# 2015PCB.net
KiCad netlist of a schematic drawn in Altium Designer
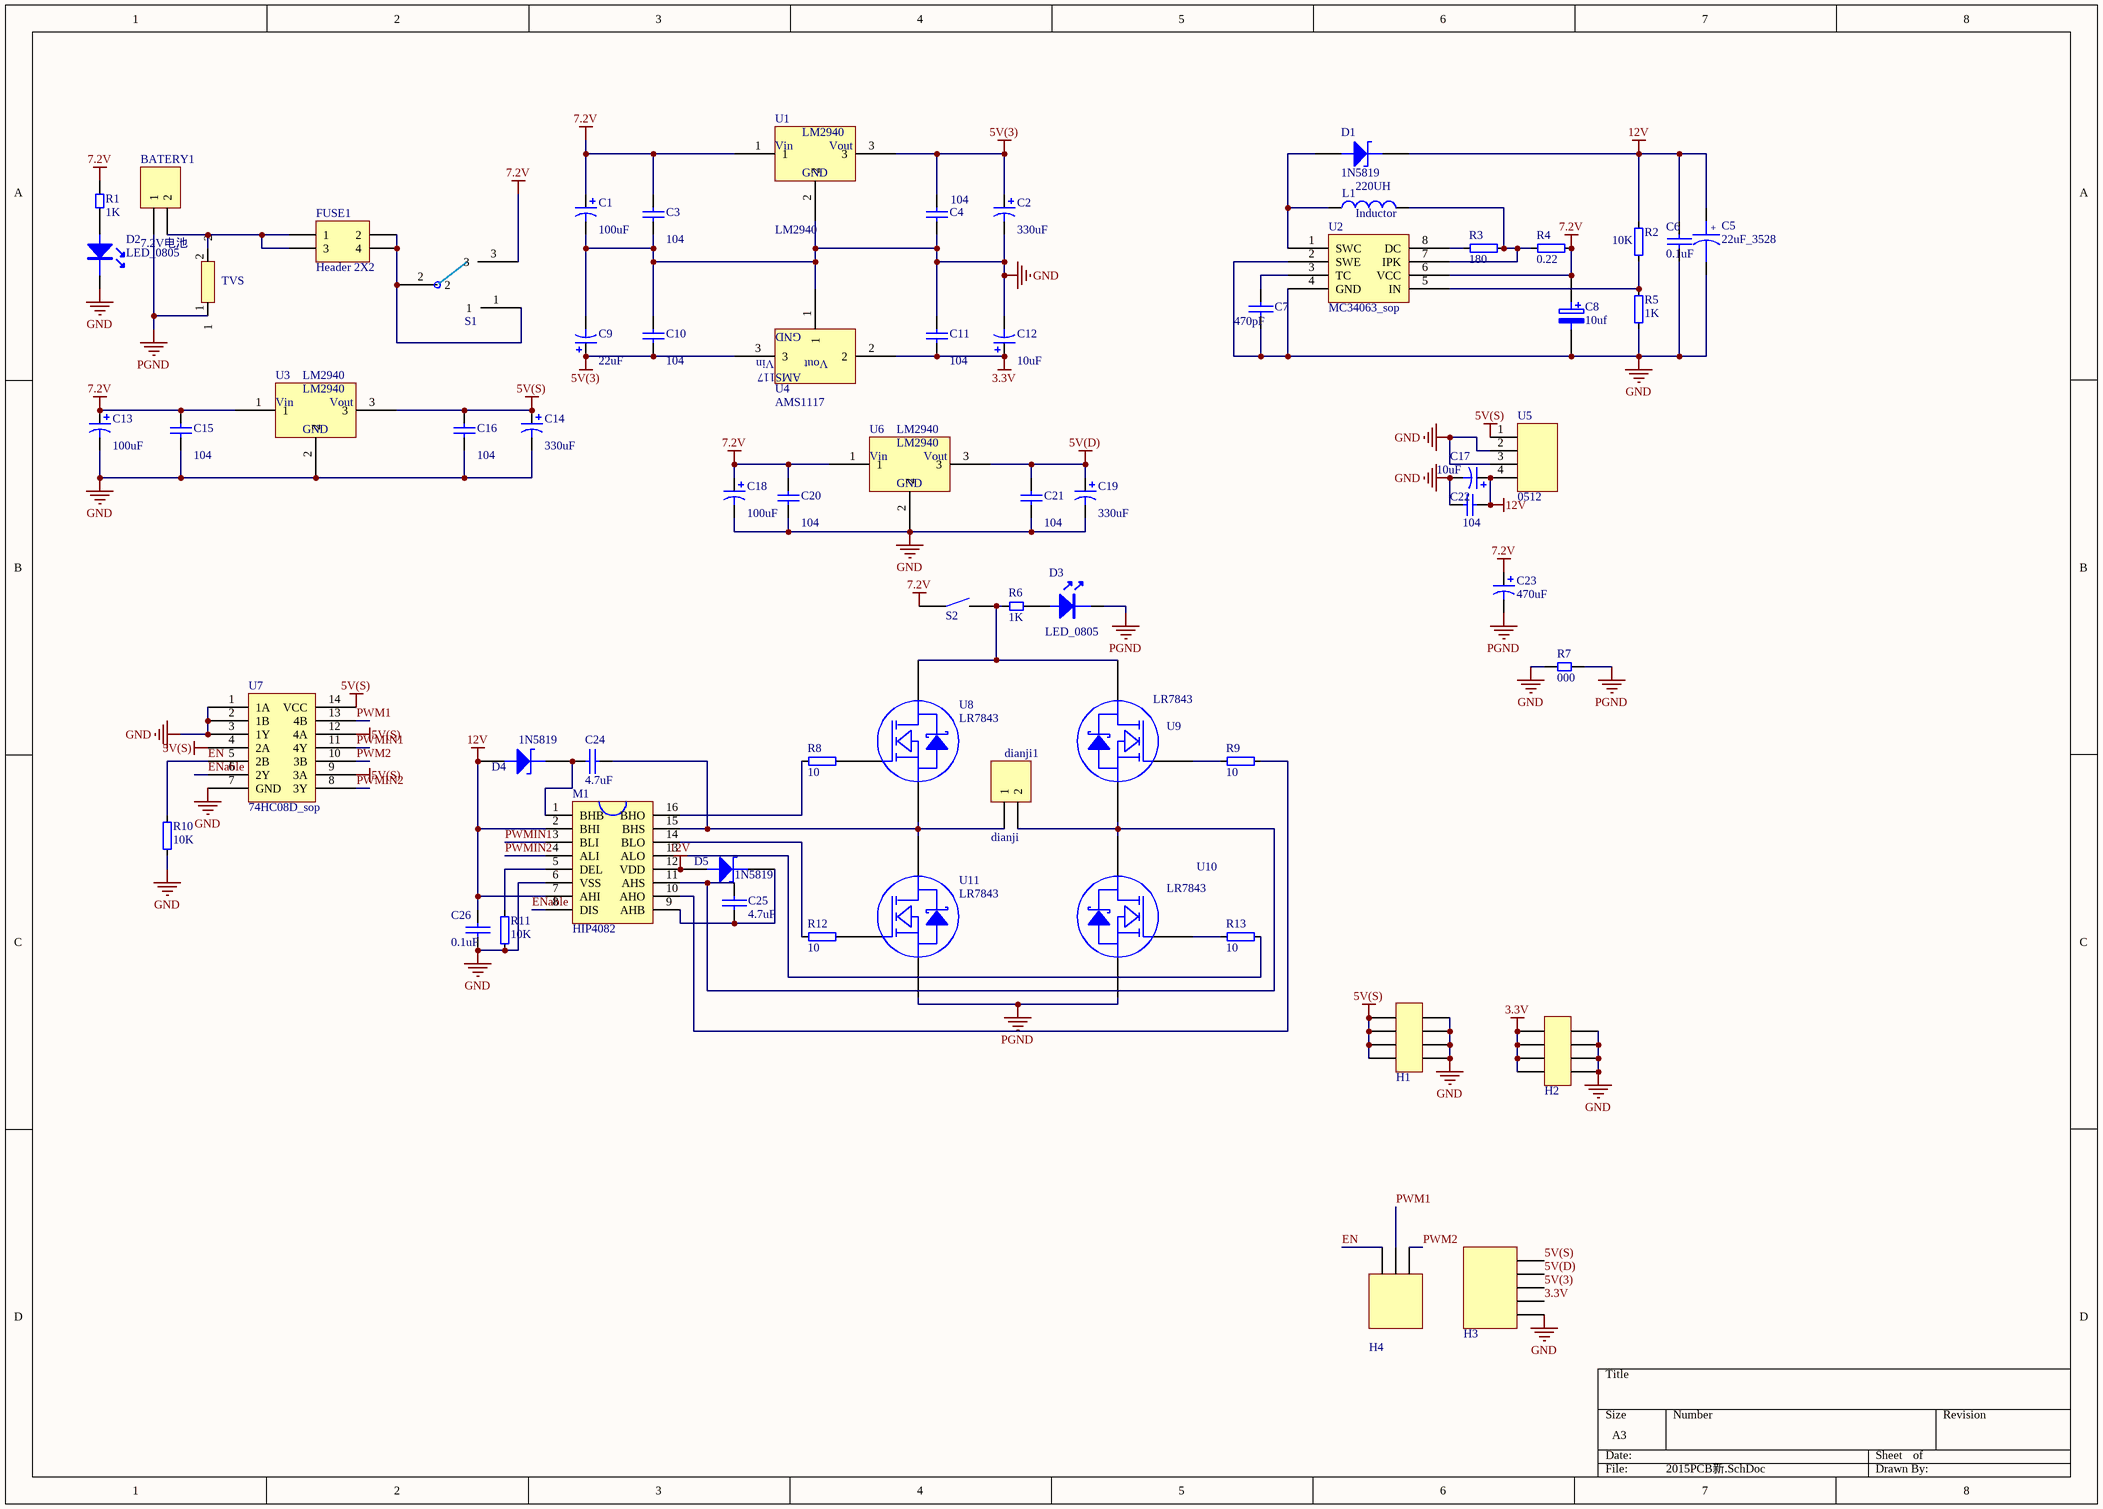
[diagram p0: 2015PCB新.SchDoc]

(export (version "E")
  (design (tool "Eeschema 10.0.6"))
  (components
    (comp (ref "BATERY1")
      (value "7.2V电池")
      (footprint "source:PCBComponent_1")
      (description "Header, 2-Pin")
      (fields (field (name "PUBLISHER") "Altium Limited"))
      (libsource (lib "hongying") (part "Header 2"))
    )
    (comp (ref "C1")
      (value "100uF")
      (footprint "Cap(pol):PCBComponent_1")
      (description "Polarized Capacitor (Radial)")
      (fields (field (name "Comment") "Cap Pol1_1") (field (name "PUBLISHER") "Altium Limited"))
      (libsource (lib "hongying") (part "Cap Pol1_1"))
    )
    (comp (ref "C2")
      (value "330uF")
      (footprint "Cap(pol):PCBComponent_1")
      (description "Polarized Capacitor (Radial)")
      (fields (field (name "Comment") "Cap Pol1_1") (field (name "PUBLISHER") "Altium Limited"))
      (libsource (lib "hongying") (part "Cap Pol1_1"))
    )
    (comp (ref "C3")
      (value "104")
      (footprint "Cap:PCBComponent_1")
      (description "Capacitor")
      (fields (field (name "Comment") "Cap") (field (name "PUBLISHER") "Altium Limited"))
      (libsource (lib "hongying") (part "Cap"))
    )
    (comp (ref "C4")
      (value "104")
      (footprint "Cap:PCBComponent_1")
      (description "Capacitor")
      (fields (field (name "Comment") "Cap") (field (name "PUBLISHER") "Altium Limited"))
      (libsource (lib "hongying") (part "Cap"))
    )
    (comp (ref "C5")
      (value "22uF_3528")
      (footprint "3528_B")
      (libsource (lib "gyh的原理图库 ") (part "10uF_3528"))
    )
    (comp (ref "C6") (value "0.1uF") (footprint "0805") (libsource (lib "gyh的原理图库 ") (part "0.1uF_0805")))
    (comp (ref "C7") (value "470pF") (footprint "0805") (libsource (lib "gyh的原理图库 ") (part "0.1uF_0805")))
    (comp (ref "C8")
      (value "10uf")
      (footprint "1206")
      (description "Electrolytic Capacitor")
      (libsource (lib "Runner") (part "ELECTRO2_2"))
    )
    (comp (ref "C9")
      (value "22uF")
      (footprint "Cap(pol):PCBComponent_1")
      (description "Polarized Capacitor (Radial)")
      (fields (field (name "Comment") "Cap Pol1_1") (field (name "PUBLISHER") "Altium Limited"))
      (libsource (lib "hongying") (part "Cap Pol1_1"))
    )
    (comp (ref "C10")
      (value "104")
      (footprint "Cap:PCBComponent_1")
      (description "Capacitor")
      (fields (field (name "Comment") "Cap") (field (name "PUBLISHER") "Altium Limited"))
      (libsource (lib "hongying") (part "Cap"))
    )
    (comp (ref "C11")
      (value "104")
      (footprint "Cap:PCBComponent_1")
      (description "Capacitor")
      (fields (field (name "Comment") "Cap") (field (name "PUBLISHER") "Altium Limited"))
      (libsource (lib "hongying") (part "Cap"))
    )
    (comp (ref "C12")
      (value "10uF")
      (footprint "Cap(pol):PCBComponent_1")
      (description "Polarized Capacitor (Radial)")
      (fields (field (name "Comment") "Cap Pol1_1") (field (name "PUBLISHER") "Altium Limited"))
      (libsource (lib "hongying") (part "Cap Pol1_1"))
    )
    (comp (ref "C13")
      (value "100uF")
      (footprint "Cap(pol):PCBComponent_1")
      (description "Polarized Capacitor (Radial)")
      (fields (field (name "Comment") "Cap Pol1_1") (field (name "PUBLISHER") "Altium Limited"))
      (libsource (lib "hongying") (part "Cap Pol1_1"))
    )
    (comp (ref "C14")
      (value "330uF")
      (footprint "Cap(pol):PCBComponent_1")
      (description "Polarized Capacitor (Radial)")
      (fields (field (name "Comment") "Cap Pol1_1") (field (name "PUBLISHER") "Altium Limited"))
      (libsource (lib "hongying") (part "Cap Pol1_1"))
    )
    (comp (ref "C15")
      (value "104")
      (footprint "Cap:PCBComponent_1")
      (description "Capacitor")
      (fields (field (name "Comment") "Cap") (field (name "PUBLISHER") "Altium Limited"))
      (libsource (lib "hongying") (part "Cap"))
    )
    (comp (ref "C16")
      (value "104")
      (footprint "Cap:PCBComponent_1")
      (description "Capacitor")
      (fields (field (name "Comment") "Cap") (field (name "PUBLISHER") "Altium Limited"))
      (libsource (lib "hongying") (part "Cap"))
    )
    (comp (ref "C17")
      (value "10uF")
      (footprint "Cap(pol):PCBComponent_1")
      (description "Polarized Capacitor (Radial)")
      (fields (field (name "Comment") "Cap Pol1_1") (field (name "PUBLISHER") "Altium Limited"))
      (libsource (lib "hongying") (part "Cap Pol1_1"))
    )
    (comp (ref "C18")
      (value "100uF")
      (footprint "Cap(pol):PCBComponent_1")
      (description "Polarized Capacitor (Radial)")
      (fields (field (name "Comment") "Cap Pol1_1") (field (name "PUBLISHER") "Altium Limited"))
      (libsource (lib "hongying") (part "Cap Pol1_1"))
    )
    (comp (ref "C19")
      (value "330uF")
      (footprint "Cap(pol):PCBComponent_1")
      (description "Polarized Capacitor (Radial)")
      (fields (field (name "Comment") "Cap Pol1_1") (field (name "PUBLISHER") "Altium Limited"))
      (libsource (lib "hongying") (part "Cap Pol1_1"))
    )
    (comp (ref "C20")
      (value "104")
      (footprint "Cap:PCBComponent_1")
      (description "Capacitor")
      (fields (field (name "Comment") "Cap") (field (name "PUBLISHER") "Altium Limited"))
      (libsource (lib "hongying") (part "Cap"))
    )
    (comp (ref "C21")
      (value "104")
      (footprint "Cap:PCBComponent_1")
      (description "Capacitor")
      (fields (field (name "Comment") "Cap") (field (name "PUBLISHER") "Altium Limited"))
      (libsource (lib "hongying") (part "Cap"))
    )
    (comp (ref "C22")
      (value "104")
      (footprint "Cap:PCBComponent_1")
      (description "Capacitor")
      (fields (field (name "Comment") "Cap") (field (name "PUBLISHER") "Altium Limited"))
      (libsource (lib "hongying") (part "Cap"))
    )
    (comp (ref "C23")
      (value "470uF")
      (footprint "Cap(pol):PCBComponent_1")
      (description "Polarized Capacitor (Radial)")
      (fields (field (name "Comment") "Cap Pol1_1") (field (name "PUBLISHER") "Altium Limited"))
      (libsource (lib "hongying") (part "Cap Pol1_1"))
    )
    (comp (ref "C24") (value "4.7uF") (footprint "0805") (libsource (lib "gyh的原理图库 ") (part "0.1uF_0805")))
    (comp (ref "C25") (value "4.7uF") (footprint "0805") (libsource (lib "gyh的原理图库 ") (part "0.1uF_0805")))
    (comp (ref "C26") (value "0.1uF") (footprint "0805") (libsource (lib "gyh的原理图库 ") (part "0.1uF_0805")))
    (comp (ref "D1")
      (value "1N5819")
      (footprint "SS14_SMA")
      (libsource (lib "gyh的原理图库 ") (part "1N5819_SMA"))
    )
    (comp (ref "D2") (value "LED_0805") (footprint "0805") (libsource (lib "gyh的原理图库 ") (part "LED_0805")))
    (comp (ref "D3") (value "LED_0805") (footprint "0805") (libsource (lib "gyh的原理图库 ") (part "LED_0805")))
    (comp (ref "D4")
      (value "1N5819")
      (footprint "SS14_SMA")
      (libsource (lib "gyh的原理图库 ") (part "1N5819_SMA"))
    )
    (comp (ref "D5")
      (value "1N5819")
      (footprint "SS14_SMA")
      (libsource (lib "gyh的原理图库 ") (part "1N5819_SMA"))
    )
    (comp (ref "dianji1")
      (value "dianji")
      (footprint "source:PCBComponent_1")
      (description "Header, 2-Pin")
      (fields (field (name "PUBLISHER") "Altium Limited"))
      (libsource (lib "hongying") (part "Header 2"))
    )
    (comp (ref "erjiguan1") (value "TVS") (footprint "1812") (libsource (lib "TVS") (part "Component_1")))
    (comp (ref "FUSE1")
      (value "Header 2X2")
      (footprint "FUSE:PCBComponent_1")
      (description "Header, 2-Pin, Dual row")
      (fields (field (name "PUBLISHER") "Altium Limited"))
      (libsource (lib "hongying") (part "Header 2X2"))
    )
    (comp (ref "H1")
      (value "HEADER4X2")
      (footprint "HEADER4X2")
      (libsource (lib "Fu的原理图库") (part "HEADER4X2"))
    )
    (comp (ref "H2")
      (value "HEADER4X2")
      (footprint "HEADER4X2")
      (libsource (lib "Fu的原理图库") (part "HEADER4X2"))
    )
    (comp (ref "H3")
      (value "HEADER")
      (footprint "HEADER5")
      (description "CCD接口")
      (libsource (lib "Fu的原理图库") (part "HEADER5"))
    )
    (comp (ref "H4") (value "HEADER") (footprint "干簧管") (libsource (lib "Fu的原理图库") (part "HEADER3")))
    (comp (ref "L1")
      (value "Inductor")
      (footprint "L(pol):PCBComponent_1")
      (fields (field (name "ALTIUM_VALUE") "220UH") (field (name "PUBLISHER") "Altium Limited"))
      (libsource (lib "Runner") (part "Inductor"))
    )
    (comp (ref "M1") (value "HIP4082") (footprint "SO-16") (libsource (lib "九届驱动电源") (part "HIP4082")))
    (comp (ref "R1")
      (value "1K")
      (footprint "0805")
      (fields (field (name "Comment") "RES"))
      (libsource (lib "Fu的原理图库") (part "0805-电阻"))
    )
    (comp (ref "R2") (value "10K") (footprint "0805") (libsource (lib "gyh的原理图库 ") (part "RES_0805")))
    (comp (ref "R3") (value "180") (footprint "0805") (libsource (lib "gyh的原理图库 ") (part "RES_0805")))
    (comp (ref "R4") (value "0.22") (footprint "0805") (libsource (lib "gyh的原理图库 ") (part "RES_0805")))
    (comp (ref "R5") (value "1K") (footprint "0805") (libsource (lib "gyh的原理图库 ") (part "RES_0805")))
    (comp (ref "R6")
      (value "1K")
      (footprint "0805")
      (fields (field (name "Comment") "RES"))
      (libsource (lib "Fu的原理图库") (part "0805-电阻"))
    )
    (comp (ref "R7")
      (value "000")
      (footprint "0805")
      (fields (field (name "Comment") "RES"))
      (libsource (lib "Fu的原理图库") (part "0805-电阻"))
    )
    (comp (ref "R8") (value "10") (footprint "0805") (libsource (lib "gyh的原理图库 ") (part "RES_0805")))
    (comp (ref "R9") (value "10") (footprint "0805") (libsource (lib "gyh的原理图库 ") (part "RES_0805")))
    (comp (ref "R10") (value "10K") (footprint "0805") (libsource (lib "gyh的原理图库 ") (part "RES_0805")))
    (comp (ref "R11") (value "10K") (footprint "0805") (libsource (lib "gyh的原理图库 ") (part "RES_0805")))
    (comp (ref "R12") (value "10") (footprint "0805") (libsource (lib "gyh的原理图库 ") (part "RES_0805")))
    (comp (ref "R13") (value "10") (footprint "0805") (libsource (lib "gyh的原理图库 ") (part "RES_0805")))
    (comp (ref "S1")
      (value "单刀双掷开关")
      (footprint "Fu的元件封装库:三脚开关")
      (libsource (lib "hongying") (part "单刀双掷开关"))
    )
    (comp (ref "S2") (value "三脚开关") (footprint "三脚开关") (libsource (lib "Fu的原理图库") (part "三脚开关")))
    (comp (ref "U1")
      (value "LM2940")
      (footprint "DIP2_2:PCBComponent_1")
      (libsource (lib "hongying") (part "LM2940"))
    )
    (comp (ref "U2")
      (value "MC34063_sop")
      (footprint "SOP-8")
      (libsource (lib "gyh的原理图库 ") (part "MC34063_sop"))
    )
    (comp (ref "U3")
      (value "LM2940")
      (footprint "DIP2_2:PCBComponent_1")
      (libsource (lib "hongying") (part "LM2940"))
    )
    (comp (ref "U4")
      (value "AMS1117")
      (footprint "SOT223_forAMS1117")
      (libsource (lib "hongying") (part "AMS1117"))
    )
    (comp (ref "U5")
      (value "0512")
      (footprint "PCBComponent_1 - duplicate")
      (libsource (lib "Fu的原理图库") (part "0512"))
    )
    (comp (ref "U6")
      (value "LM2940")
      (footprint "DIP2_2:PCBComponent_1")
      (libsource (lib "hongying") (part "LM2940"))
    )
    (comp (ref "U7")
      (value "74HC08D_sop")
      (footprint "SOP-14")
      (libsource (lib "gyh的原理图库 ") (part "74HCT00D_sop"))
    )
    (comp (ref "U8") (value "LR7843") (footprint "DPAK") (libsource (lib "gyh的原理图库 ") (part "IRF3205_D2PAK")))
    (comp (ref "U9") (value "LR7843") (footprint "DPAK") (libsource (lib "gyh的原理图库 ") (part "IRF3205_D2PAK")))
    (comp (ref "U10")
      (value "LR7843")
      (footprint "DPAK")
      (libsource (lib "gyh的原理图库 ") (part "IRF3205_D2PAK"))
    )
    (comp (ref "U11")
      (value "LR7843")
      (footprint "DPAK")
      (libsource (lib "gyh的原理图库 ") (part "IRF3205_D2PAK"))
    )
  )
  (nets
    (net (code "1") (name "/EN") (class "Default")
      (node (ref "H4") (pin "3") (pinfunction "3_3") (pintype "passive"))
      (node (ref "R10") (pin "2") (pinfunction "2_2") (pintype "passive"))
      (node (ref "U7") (pin "5") (pinfunction "2B_5") (pintype "passive"))
    )
    (net (code "2") (name "/ENable") (class "Default")
      (node (ref "M1") (pin "8") (pinfunction "DIS_8") (pintype "passive"))
      (node (ref "U7") (pin "6") (pinfunction "2Y_6") (pintype "passive"))
    )
    (net (code "3") (name "/PWM1") (class "Default")
      (node (ref "H4") (pin "2") (pinfunction "2_2") (pintype "passive"))
      (node (ref "U7") (pin "13") (pinfunction "4B_13") (pintype "passive"))
    )
    (net (code "4") (name "/PWM2") (class "Default")
      (node (ref "H4") (pin "1") (pinfunction "1_1") (pintype "passive"))
      (node (ref "U7") (pin "10") (pinfunction "3B_10") (pintype "passive"))
    )
    (net (code "5") (name "/PWMIN1") (class "Default")
      (node (ref "M1") (pin "3") (pinfunction "BLI_3") (pintype "passive"))
      (node (ref "U7") (pin "11") (pinfunction "4Y_11") (pintype "passive"))
    )
    (net (code "6") (name "/PWMIN2") (class "Default")
      (node (ref "M1") (pin "4") (pinfunction "ALI_4") (pintype "passive"))
      (node (ref "U7") (pin "8") (pinfunction "3Y_8") (pintype "passive"))
    )
    (net (code "7") (name "3.3V") (class "Default")
      (node (ref "C11") (pin "1") (pinfunction "1_1") (pintype "passive"))
      (node (ref "C12") (pin "1") (pinfunction "1_1") (pintype "passive"))
      (node (ref "H2") (pin "1") (pinfunction "1_1") (pintype "passive"))
      (node (ref "H2") (pin "2") (pinfunction "2_2") (pintype "passive"))
      (node (ref "H2") (pin "3") (pinfunction "3_3") (pintype "passive"))
      (node (ref "H2") (pin "4") (pinfunction "4_4") (pintype "passive"))
      (node (ref "H3") (pin "2") (pinfunction "2_2") (pintype "passive"))
      (node (ref "U4") (pin "2") (pinfunction "2_2") (pintype "passive"))
    )
    (net (code "8") (name "5V(3)") (class "Default")
      (node (ref "C10") (pin "1") (pinfunction "1_1") (pintype "passive"))
      (node (ref "C2") (pin "1") (pinfunction "1_1") (pintype "passive"))
      (node (ref "C4") (pin "2") (pinfunction "2_2") (pintype "passive"))
      (node (ref "C9") (pin "1") (pinfunction "1_1") (pintype "passive"))
      (node (ref "H3") (pin "3") (pinfunction "3_3") (pintype "passive"))
      (node (ref "U1") (pin "3") (pinfunction "3_3") (pintype "passive"))
      (node (ref "U4") (pin "3") (pinfunction "3_3") (pintype "passive"))
    )
    (net (code "9") (name "5V(D)") (class "Default")
      (node (ref "C19") (pin "1") (pinfunction "1_1") (pintype "passive"))
      (node (ref "C21") (pin "2") (pinfunction "2_2") (pintype "passive"))
      (node (ref "H3") (pin "4") (pinfunction "4_4") (pintype "passive"))
      (node (ref "U6") (pin "3") (pinfunction "3_3") (pintype "passive"))
    )
    (net (code "10") (name "5V(S)") (class "Default")
      (node (ref "C14") (pin "1") (pinfunction "1_1") (pintype "passive"))
      (node (ref "C16") (pin "2") (pinfunction "2_2") (pintype "passive"))
      (node (ref "H1") (pin "1") (pinfunction "1_1") (pintype "passive"))
      (node (ref "H1") (pin "2") (pinfunction "2_2") (pintype "passive"))
      (node (ref "H1") (pin "3") (pinfunction "3_3") (pintype "passive"))
      (node (ref "H1") (pin "4") (pinfunction "4_4") (pintype "passive"))
      (node (ref "H3") (pin "5") (pinfunction "5_5") (pintype "passive"))
      (node (ref "U3") (pin "3") (pinfunction "3_3") (pintype "passive"))
      (node (ref "U5") (pin "1") (pintype "passive"))
      (node (ref "U7") (pin "12") (pinfunction "4A_12") (pintype "passive"))
      (node (ref "U7") (pin "14") (pinfunction "VCC_14") (pintype "passive"))
      (node (ref "U7") (pin "4") (pinfunction "2A_4") (pintype "passive"))
      (node (ref "U7") (pin "9") (pinfunction "3A_9") (pintype "passive"))
    )
    (net (code "11") (name "7.2V") (class "Default")
      (node (ref "C1") (pin "1") (pinfunction "1_1") (pintype "passive"))
      (node (ref "C13") (pin "1") (pinfunction "1_1") (pintype "passive"))
      (node (ref "C15") (pin "2") (pinfunction "2_2") (pintype "passive"))
      (node (ref "C18") (pin "1") (pinfunction "1_1") (pintype "passive"))
      (node (ref "C20") (pin "2") (pinfunction "2_2") (pintype "passive"))
      (node (ref "C23") (pin "1") (pinfunction "1_1") (pintype "passive"))
      (node (ref "C3") (pin "2") (pinfunction "2_2") (pintype "passive"))
      (node (ref "C8") (pin "1") (pinfunction "1_1") (pintype "passive"))
      (node (ref "R1") (pin "1") (pinfunction "1_1") (pintype "passive"))
      (node (ref "R4") (pin "2") (pinfunction "2_2") (pintype "passive"))
      (node (ref "S1") (pin "3") (pinfunction "3_3") (pintype "passive"))
      (node (ref "S2") (pin "2") (pinfunction "COMMON_2") (pintype "passive"))
      (node (ref "U1") (pin "1") (pinfunction "1_1") (pintype "passive"))
      (node (ref "U2") (pin "6") (pinfunction "VCC_6") (pintype "passive"))
      (node (ref "U3") (pin "1") (pinfunction "1_1") (pintype "passive"))
      (node (ref "U6") (pin "1") (pinfunction "1_1") (pintype "passive"))
    )
    (net (code "12") (name "12V") (class "Default")
      (node (ref "C17") (pin "1") (pinfunction "1_1") (pintype "passive"))
      (node (ref "C22") (pin "1") (pinfunction "1_1") (pintype "passive"))
      (node (ref "C26") (pin "1") (pinfunction "1_1") (pintype "passive"))
      (node (ref "C5") (pin "1") (pinfunction "1_1") (pintype "passive"))
      (node (ref "C6") (pin "1") (pinfunction "1_1") (pintype "passive"))
      (node (ref "D1") (pin "2") (pinfunction "K_2") (pintype "passive"))
      (node (ref "D4") (pin "1") (pinfunction "A_1") (pintype "passive"))
      (node (ref "D5") (pin "1") (pinfunction "A_1") (pintype "passive"))
      (node (ref "M1") (pin "12") (pinfunction "VDD_12") (pintype "passive"))
      (node (ref "M1") (pin "2") (pinfunction "BHI_2") (pintype "passive"))
      (node (ref "M1") (pin "7") (pinfunction "AHI_7") (pintype "passive"))
      (node (ref "R2") (pin "1") (pinfunction "1_1") (pintype "passive"))
      (node (ref "U5") (pin "4") (pinfunction "HR_4") (pintype "passive"))
    )
    (net (code "13") (name "GND") (class "Default")
      (node (ref "C1") (pin "2") (pinfunction "2_2") (pintype "passive"))
      (node (ref "C10") (pin "2") (pinfunction "2_2") (pintype "passive"))
      (node (ref "C11") (pin "2") (pinfunction "2_2") (pintype "passive"))
      (node (ref "C12") (pin "2") (pinfunction "2_2") (pintype "passive"))
      (node (ref "C13") (pin "2") (pinfunction "2_2") (pintype "passive"))
      (node (ref "C14") (pin "2") (pinfunction "2_2") (pintype "passive"))
      (node (ref "C15") (pin "1") (pinfunction "1_1") (pintype "passive"))
      (node (ref "C16") (pin "1") (pinfunction "1_1") (pintype "passive"))
      (node (ref "C17") (pin "2") (pinfunction "2_2") (pintype "passive"))
      (node (ref "C18") (pin "2") (pinfunction "2_2") (pintype "passive"))
      (node (ref "C19") (pin "2") (pinfunction "2_2") (pintype "passive"))
      (node (ref "C2") (pin "2") (pinfunction "2_2") (pintype "passive"))
      (node (ref "C20") (pin "1") (pinfunction "1_1") (pintype "passive"))
      (node (ref "C21") (pin "1") (pinfunction "1_1") (pintype "passive"))
      (node (ref "C22") (pin "2") (pinfunction "2_2") (pintype "passive"))
      (node (ref "C26") (pin "2") (pinfunction "2_2") (pintype "passive"))
      (node (ref "C3") (pin "1") (pinfunction "1_1") (pintype "passive"))
      (node (ref "C4") (pin "1") (pinfunction "1_1") (pintype "passive"))
      (node (ref "C5") (pin "2") (pinfunction "2_2") (pintype "passive"))
      (node (ref "C6") (pin "2") (pinfunction "2_2") (pintype "passive"))
      (node (ref "C7") (pin "2") (pinfunction "2_2") (pintype "passive"))
      (node (ref "C8") (pin "2") (pinfunction "2_2") (pintype "passive"))
      (node (ref "C9") (pin "2") (pinfunction "2_2") (pintype "passive"))
      (node (ref "D2") (pin "2") (pinfunction "2_2") (pintype "passive"))
      (node (ref "H1") (pin "5") (pinfunction "5_5") (pintype "passive"))
      (node (ref "H1") (pin "6") (pinfunction "6_6") (pintype "passive"))
      (node (ref "H1") (pin "7") (pinfunction "7_7") (pintype "passive"))
      (node (ref "H1") (pin "8") (pinfunction "8_8") (pintype "passive"))
      (node (ref "H2") (pin "5") (pinfunction "5_5") (pintype "passive"))
      (node (ref "H2") (pin "6") (pinfunction "6_6") (pintype "passive"))
      (node (ref "H2") (pin "7") (pinfunction "7_7") (pintype "passive"))
      (node (ref "H2") (pin "8") (pinfunction "8_8") (pintype "passive"))
      (node (ref "H3") (pin "1") (pinfunction "1_1") (pintype "passive"))
      (node (ref "M1") (pin "6") (pinfunction "VSS_6") (pintype "passive"))
      (node (ref "R10") (pin "1") (pinfunction "1_1") (pintype "passive"))
      (node (ref "R11") (pin "1") (pinfunction "1_1") (pintype "passive"))
      (node (ref "R5") (pin "1") (pinfunction "1_1") (pintype "passive"))
      (node (ref "R7") (pin "1") (pinfunction "1_1") (pintype "passive"))
      (node (ref "U1") (pin "2") (pinfunction "2_2") (pintype "passive"))
      (node (ref "U2") (pin "2") (pinfunction "SWE_2") (pintype "passive"))
      (node (ref "U2") (pin "4") (pinfunction "GND_4") (pintype "passive"))
      (node (ref "U3") (pin "2") (pinfunction "2_2") (pintype "passive"))
      (node (ref "U4") (pin "1") (pinfunction "1_1") (pintype "passive"))
      (node (ref "U5") (pin "2") (pinfunction "HL_2") (pintype "passive"))
      (node (ref "U5") (pin "3") (pinfunction "HM_3") (pintype "passive"))
      (node (ref "U6") (pin "2") (pinfunction "2_2") (pintype "passive"))
      (node (ref "U7") (pin "1") (pinfunction "1A_1") (pintype "passive"))
      (node (ref "U7") (pin "2") (pinfunction "1B_2") (pintype "passive"))
      (node (ref "U7") (pin "3") (pinfunction "1Y_3") (pintype "passive"))
      (node (ref "U7") (pin "7") (pinfunction "GND_7") (pintype "passive"))
    )
    (net (code "14") (name "Net-(BATERY1-Pad2)") (class "Default")
      (node (ref "BATERY1") (pin "2") (pinfunction "2_2") (pintype "passive"))
      (node (ref "FUSE1") (pin "1") (pinfunction "1_1") (pintype "passive"))
      (node (ref "FUSE1") (pin "3") (pinfunction "3_3") (pintype "passive"))
    )
    (net (code "15") (name "Net-(D1-A)") (class "Default")
      (node (ref "D1") (pin "1") (pinfunction "A_1") (pintype "passive"))
      (node (ref "L1") (pin "1") (pinfunction "1_1") (pintype "passive"))
      (node (ref "U2") (pin "1") (pinfunction "SWC_1") (pintype "passive"))
    )
    (net (code "16") (name "Net-(D2-Pad1)") (class "Default")
      (node (ref "D2") (pin "1") (pinfunction "1_1") (pintype "passive"))
      (node (ref "R1") (pin "2") (pinfunction "2_2") (pintype "passive"))
    )
    (net (code "17") (name "Net-(D3-Pad1)") (class "Default")
      (node (ref "D3") (pin "1") (pinfunction "1_1") (pintype "passive"))
      (node (ref "R6") (pin "2") (pinfunction "2_2") (pintype "passive"))
    )
    (net (code "18") (name "Net-(D4-K)") (class "Default")
      (node (ref "C24") (pin "2") (pinfunction "2_2") (pintype "passive"))
      (node (ref "D4") (pin "2") (pinfunction "K_2") (pintype "passive"))
      (node (ref "M1") (pin "1") (pinfunction "BHB_1") (pintype "passive"))
    )
    (net (code "19") (name "Net-(D5-K)") (class "Default")
      (node (ref "C25") (pin "2") (pinfunction "2_2") (pintype "passive"))
      (node (ref "D5") (pin "2") (pinfunction "K_2") (pintype "passive"))
      (node (ref "M1") (pin "9") (pinfunction "AHB_9") (pintype "passive"))
    )
    (net (code "20") (name "Net-(FUSE1-Pad2)") (class "Default")
      (node (ref "FUSE1") (pin "2") (pinfunction "2_2") (pintype "passive"))
      (node (ref "FUSE1") (pin "4") (pinfunction "4_4") (pintype "passive"))
      (node (ref "S1") (pin "1") (pinfunction "1_1") (pintype "passive"))
      (node (ref "S1") (pin "2") (pinfunction "2_2") (pintype "passive"))
    )
    (net (code "21") (name "Net-(M1-AHO)") (class "Default")
      (node (ref "M1") (pin "10") (pinfunction "AHO_10") (pintype "passive"))
      (node (ref "R9") (pin "2") (pinfunction "2_2") (pintype "passive"))
    )
    (net (code "22") (name "Net-(M1-AHS)") (class "Default")
      (node (ref "C25") (pin "1") (pinfunction "1_1") (pintype "passive"))
      (node (ref "M1") (pin "11") (pinfunction "AHS_11") (pintype "passive"))
      (node (ref "U10") (pin "2") (pinfunction "D_2") (pintype "passive"))
      (node (ref "U9") (pin "3") (pinfunction "S_3") (pintype "passive"))
      (node (ref "dianji1") (pin "2") (pinfunction "2_2") (pintype "passive"))
    )
    (net (code "23") (name "Net-(M1-ALO)") (class "Default")
      (node (ref "M1") (pin "13") (pinfunction "ALO_13") (pintype "passive"))
      (node (ref "R13") (pin "2") (pinfunction "2_2") (pintype "passive"))
    )
    (net (code "24") (name "Net-(M1-BHO)") (class "Default")
      (node (ref "M1") (pin "16") (pinfunction "BHO_16") (pintype "passive"))
      (node (ref "R8") (pin "1") (pinfunction "1_1") (pintype "passive"))
    )
    (net (code "25") (name "Net-(M1-BHS)") (class "Default")
      (node (ref "C24") (pin "1") (pinfunction "1_1") (pintype "passive"))
      (node (ref "M1") (pin "15") (pinfunction "BHS_15") (pintype "passive"))
      (node (ref "U11") (pin "2") (pinfunction "D_2") (pintype "passive"))
      (node (ref "U8") (pin "3") (pinfunction "S_3") (pintype "passive"))
      (node (ref "dianji1") (pin "1") (pinfunction "1_1") (pintype "passive"))
    )
    (net (code "26") (name "Net-(M1-BLO)") (class "Default")
      (node (ref "M1") (pin "14") (pinfunction "BLO_14") (pintype "passive"))
      (node (ref "R12") (pin "1") (pinfunction "1_1") (pintype "passive"))
    )
    (net (code "27") (name "Net-(M1-DEL)") (class "Default")
      (node (ref "M1") (pin "5") (pinfunction "DEL_5") (pintype "passive"))
      (node (ref "R11") (pin "2") (pinfunction "2_2") (pintype "passive"))
    )
    (net (code "28") (name "Net-(S2-ON)") (class "Default")
      (node (ref "R6") (pin "1") (pinfunction "1_1") (pintype "passive"))
      (node (ref "S2") (pin "3") (pinfunction "ON_3") (pintype "passive"))
      (node (ref "U8") (pin "2") (pinfunction "D_2") (pintype "passive"))
      (node (ref "U9") (pin "2") (pinfunction "D_2") (pintype "passive"))
    )
    (net (code "29") (name "Net-(U2-DC)") (class "Default")
      (node (ref "R3") (pin "1") (pinfunction "1_1") (pintype "passive"))
      (node (ref "U2") (pin "8") (pinfunction "DC_8") (pintype "passive"))
    )
    (net (code "30") (name "Net-(U2-IN)") (class "Default")
      (node (ref "R2") (pin "2") (pinfunction "2_2") (pintype "passive"))
      (node (ref "R5") (pin "2") (pinfunction "2_2") (pintype "passive"))
      (node (ref "U2") (pin "5") (pinfunction "IN_5") (pintype "passive"))
    )
    (net (code "31") (name "Net-(U2-IPK)") (class "Default")
      (node (ref "L1") (pin "2") (pinfunction "2_2") (pintype "passive"))
      (node (ref "R3") (pin "2") (pinfunction "2_2") (pintype "passive"))
      (node (ref "R4") (pin "1") (pinfunction "1_1") (pintype "passive"))
      (node (ref "U2") (pin "7") (pinfunction "IPK_7") (pintype "passive"))
    )
    (net (code "32") (name "Net-(U2-TC)") (class "Default")
      (node (ref "C7") (pin "1") (pinfunction "1_1") (pintype "passive"))
      (node (ref "U2") (pin "3") (pinfunction "TC_3") (pintype "passive"))
    )
    (net (code "33") (name "Net-(U8-G)") (class "Default")
      (node (ref "R8") (pin "2") (pinfunction "2_2") (pintype "passive"))
      (node (ref "U8") (pin "1") (pinfunction "G_1") (pintype "passive"))
    )
    (net (code "34") (name "Net-(U9-G)") (class "Default")
      (node (ref "R9") (pin "1") (pinfunction "1_1") (pintype "passive"))
      (node (ref "U9") (pin "1") (pinfunction "G_1") (pintype "passive"))
    )
    (net (code "35") (name "Net-(U10-G)") (class "Default")
      (node (ref "R13") (pin "1") (pinfunction "1_1") (pintype "passive"))
      (node (ref "U10") (pin "1") (pinfunction "G_1") (pintype "passive"))
    )
    (net (code "36") (name "Net-(U11-G)") (class "Default")
      (node (ref "R12") (pin "2") (pinfunction "2_2") (pintype "passive"))
      (node (ref "U11") (pin "1") (pinfunction "G_1") (pintype "passive"))
    )
    (net (code "37") (name "PGND") (class "Default")
      (node (ref "BATERY1") (pin "1") (pinfunction "1_1") (pintype "passive"))
      (node (ref "C23") (pin "2") (pinfunction "2_2") (pintype "passive"))
      (node (ref "D3") (pin "2") (pinfunction "2_2") (pintype "passive"))
      (node (ref "R7") (pin "2") (pinfunction "2_2") (pintype "passive"))
      (node (ref "U10") (pin "3") (pinfunction "S_3") (pintype "passive"))
      (node (ref "U11") (pin "3") (pinfunction "S_3") (pintype "passive"))
    )
    (net (code "38") (name "unconnected-(S2-NC-Pad1)") (class "Default")
      (node (ref "S2") (pin "1") (pinfunction "NC_1") (pintype "passive"))
    )
    (net (code "39") (name "unconnected-(erjiguan1-Pad1)") (class "Default")
      (node (ref "erjiguan1") (pin "1") (pinfunction "1_1") (pintype "passive"))
    )
    (net (code "40") (name "unconnected-(erjiguan1-Pad2)") (class "Default")
      (node (ref "erjiguan1") (pin "2") (pinfunction "2_2") (pintype "passive"))
    )
  )
)
